# connector1.net
KiCad netlist of a schematic drawn in Altium Designer
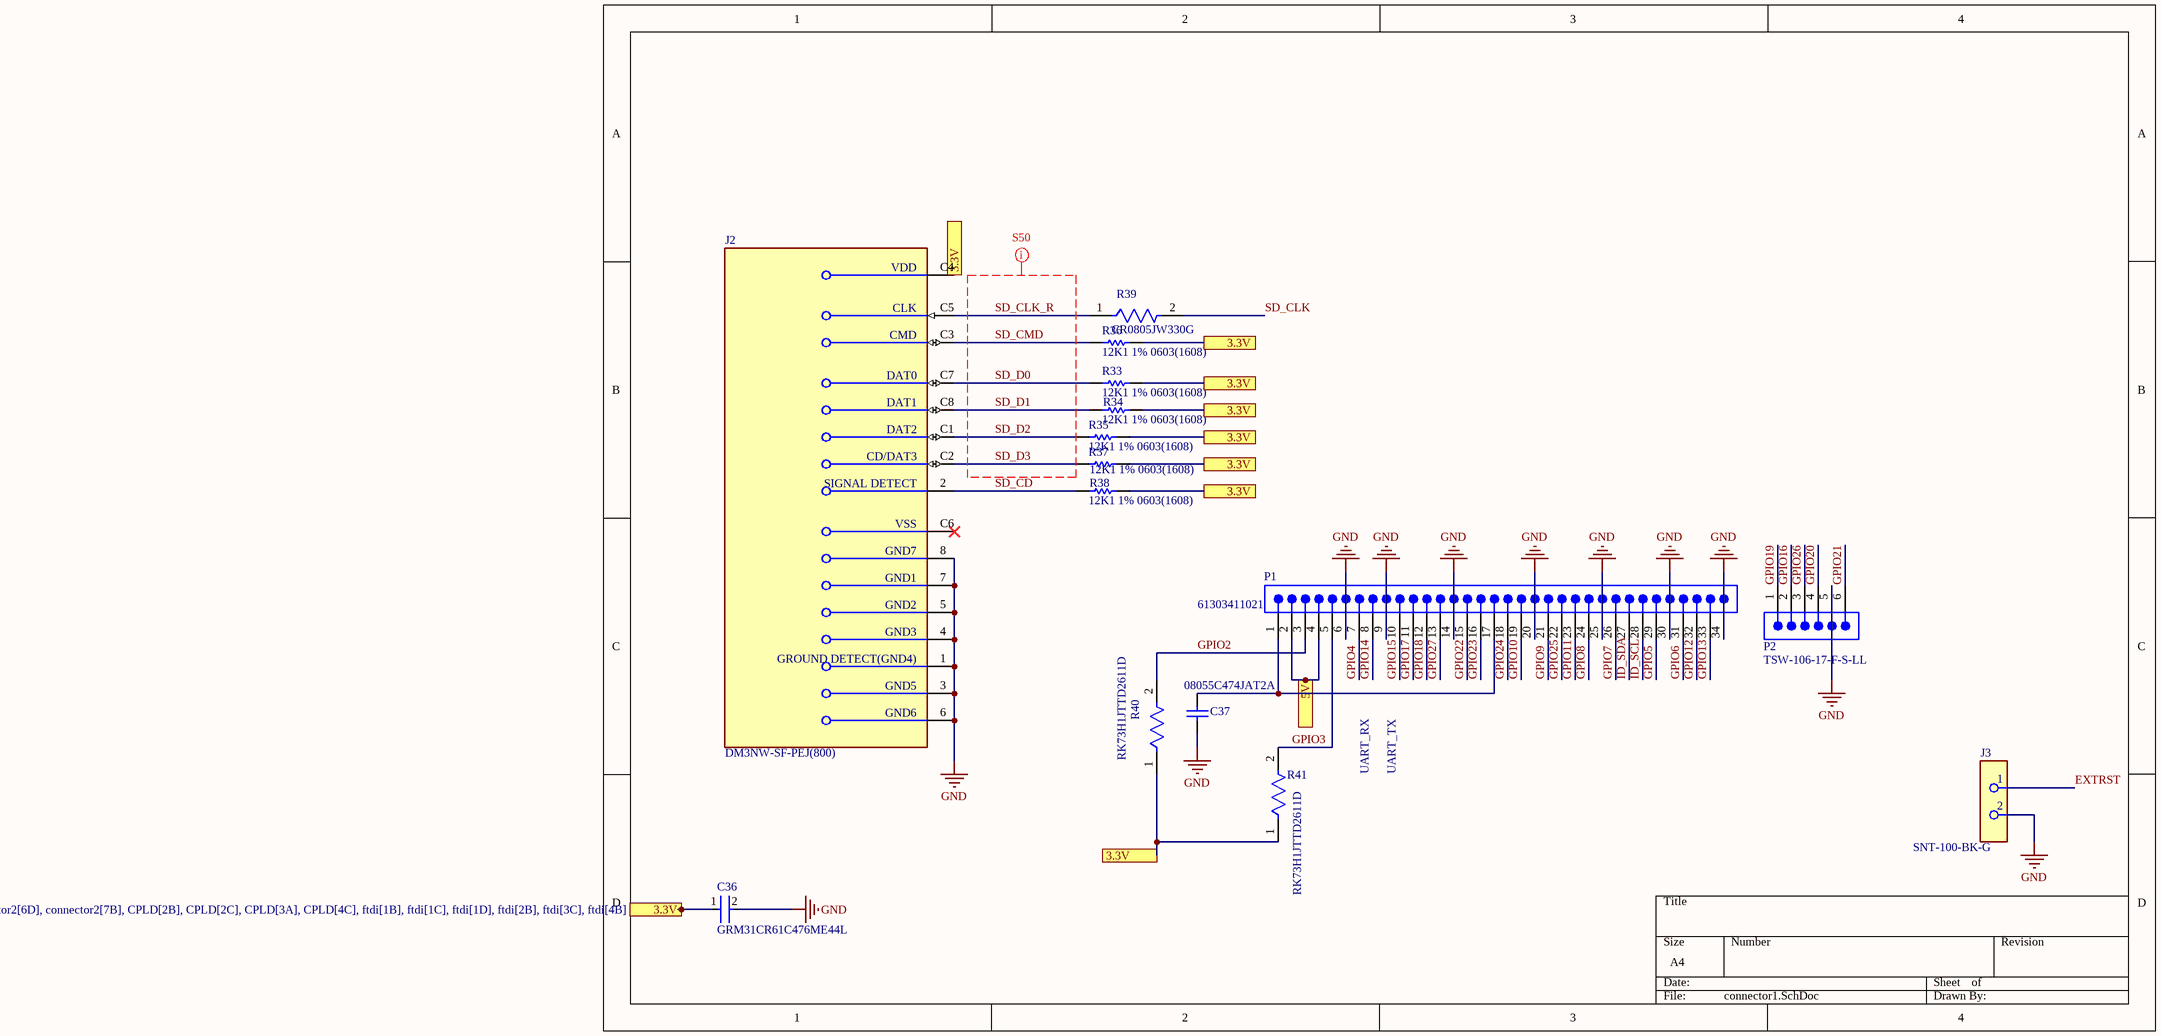
[diagram p0: connector1.SchDoc]

(export (version "E")
  (design (tool "Eeschema 10.0.6"))
  (components
    (comp (ref "C36")
      (value "GRM31CR61C476ME44L")
      (footprint "FP-GRM31C-0_3-e0_3_0_8-IPC_C")
      (description "Chip Multilayer Ceramic Capacitors for General Purpose, 1206, 47uF, X5R, 15%, 20%, 16V")
      (fields (field (name "TOLERANCE") "20%"))
      (libsource (lib "Altium Content Vault") (part "f23184f103b6ebe33a8c269c53dcba6"))
    )
    (comp (ref "C37")
      (value "08055C474JAT2A")
      (footprint "CAPC2013X140X50ML20T25")
      (fields (field (name "MANUFACTURER") "AVX Interconnect / Elco"))
      (libsource (lib "Altium Content Vault") (part "CAP"))
    )
    (comp (ref "J2")
      (value "DM3NW-SF-PEJ(800)")
      (footprint "FP-DM3NW-SF-PEJ_800-MFG")
      (description "CONN MICROSD CARD PUSH-PUSH SMD")
      (libsource (lib "Altium Content Vault") (part "c4d74c69e72bf12f873f0521b7ad6d9"))
    )
    (comp (ref "J3")
      (value "SNT-100-BK-G")
      (footprint "FP-SNT-100-BK-G-MFG")
      (description "CONN SHUNT 2POS")
      (libsource (lib "Altium Content Vault") (part "245d4dded57b275ea2dfe9722bb6e84"))
    )
    (comp (ref "P1")
      (value "61303411021")
      (footprint "61303411021")
      (libsource (lib "Altium Content Vault") (part "Header_Male_1R_34P"))
    )
    (comp (ref "P2")
      (value "TSW-106-17-F-S-LL")
      (footprint "SMTC-TSW-106-17-X-S-LL")
      (description "0.025\" SQ Post Header, Through-hole, Vertical, -55 to 125 degC, 2.54 mm Pitch, 6-Pin, Male, RoHS")
      (fields (field (name "MANUFACTURER") "Samtec"))
      (libsource (lib "Altium Content Vault") (part "SMTC-TSW-106-X-X-S-X"))
    )
    (comp (ref "R33")
      (value "12K1 1% 0603(1608)")
      (footprint "RESC0603(1608)_M")
      (description "12K1 0.1W 1% 0603 (1608 Metric)  SMD")
      (fields (field (name "POWER") "0.1 W") (field (name "TOLERANCE") "1 %"))
      (libsource (lib "Altium Content Vault") (part "RES"))
    )
    (comp (ref "R34")
      (value "12K1 1% 0603(1608)")
      (footprint "RESC0603(1608)_M")
      (description "12K1 0.1W 1% 0603 (1608 Metric)  SMD")
      (fields (field (name "POWER") "0.1 W") (field (name "TOLERANCE") "1 %"))
      (libsource (lib "Altium Content Vault") (part "RES"))
    )
    (comp (ref "R35")
      (value "12K1 1% 0603(1608)")
      (footprint "RESC0603(1608)_M")
      (description "12K1 0.1W 1% 0603 (1608 Metric)  SMD")
      (fields (field (name "POWER") "0.1 W") (field (name "TOLERANCE") "1 %"))
      (libsource (lib "Altium Content Vault") (part "RES"))
    )
    (comp (ref "R36")
      (value "12K1 1% 0603(1608)")
      (footprint "RESC0603(1608)_M")
      (description "12K1 0.1W 1% 0603 (1608 Metric)  SMD")
      (fields (field (name "POWER") "0.1 W") (field (name "TOLERANCE") "1 %"))
      (libsource (lib "Altium Content Vault") (part "RES"))
    )
    (comp (ref "R37")
      (value "12K1 1% 0603(1608)")
      (footprint "RESC0603(1608)_M")
      (description "12K1 0.1W 1% 0603 (1608 Metric)  SMD")
      (fields (field (name "POWER") "0.1 W") (field (name "TOLERANCE") "1 %"))
      (libsource (lib "Altium Content Vault") (part "RES"))
    )
    (comp (ref "R38")
      (value "12K1 1% 0603(1608)")
      (footprint "RESC0603(1608)_M")
      (description "12K1 0.1W 1% 0603 (1608 Metric)  SMD")
      (fields (field (name "POWER") "0.1 W") (field (name "TOLERANCE") "1 %"))
      (libsource (lib "Altium Content Vault") (part "RES"))
    )
    (comp (ref "R39")
      (value "CR0805JW330G")
      (footprint "FP-CR0805-IPC_C")
      (description "Thick Film Chip Resistors 0805 33Ω 0.125W 5% 200ppm/°C")
      (fields (field (name "TOLERANCE") "5%"))
      (libsource (lib "Altium Content Vault") (part "1029c3af85768c4190bb7ad29bc67b5"))
    )
    (comp (ref "R40")
      (value "RK73H1JTTD2611D")
      (footprint "FP-RK73H1J-IPC_B")
      (description "2.61kΩ ±0.5% 0.1W Chip Resistor 0603 Thick Film AEC-Q200 Qualified")
      (libsource (lib "Altium Content Vault") (part "1029c3af85768c4190bb7ad29bc67b5"))
    )
    (comp (ref "R41")
      (value "RK73H1JTTD2611D")
      (footprint "FP-RK73H1J-IPC_B")
      (description "2.61kΩ ±0.5% 0.1W Chip Resistor 0603 Thick Film AEC-Q200 Qualified")
      (libsource (lib "Altium Content Vault") (part "1029c3af85768c4190bb7ad29bc67b5"))
    )
  )
  (nets
    (net (code "1") (name "/3.3V") (class "Default")
      (node (ref "C36") (pin "1") (pinfunction "1_1") (pintype "passive"))
      (node (ref "J2") (pin "C4") (pinfunction "VDD_C4") (pintype "power_in"))
      (node (ref "R33") (pin "2") (pinfunction "2_2") (pintype "passive"))
      (node (ref "R34") (pin "2") (pinfunction "2_2") (pintype "passive"))
      (node (ref "R35") (pin "2") (pinfunction "2_2") (pintype "passive"))
      (node (ref "R36") (pin "2") (pinfunction "2_2") (pintype "passive"))
      (node (ref "R37") (pin "2") (pinfunction "2_2") (pintype "passive"))
      (node (ref "R38") (pin "2") (pinfunction "2_2") (pintype "passive"))
      (node (ref "R40") (pin "1") (pinfunction "1_1") (pintype "passive"))
      (node (ref "R41") (pin "1") (pinfunction "1_1") (pintype "passive"))
    )
    (net (code "2") (name "/5V") (class "Default")
      (node (ref "P1") (pin "2") (pinfunction "2_2") (pintype "passive"))
      (node (ref "P1") (pin "4") (pinfunction "4_4") (pintype "passive"))
    )
    (net (code "4") (name "/GPIO2") (class "Default")
      (node (ref "P1") (pin "3") (pinfunction "3_3") (pintype "passive"))
      (node (ref "R40") (pin "2") (pinfunction "2_2") (pintype "passive"))
    )
    (net (code "5") (name "/GPIO3") (class "Default")
      (node (ref "P1") (pin "5") (pinfunction "5_5") (pintype "passive"))
      (node (ref "R41") (pin "2") (pinfunction "2_2") (pintype "passive"))
    )
    (net (code "6") (name "/GPIO4") (class "Default")
      (node (ref "P1") (pin "7") (pinfunction "7_7") (pintype "passive"))
    )
    (net (code "7") (name "/GPIO5") (class "Default")
      (node (ref "P1") (pin "29") (pinfunction "29_29") (pintype "passive"))
    )
    (net (code "8") (name "/GPIO6") (class "Default")
      (node (ref "P1") (pin "31") (pinfunction "31_31") (pintype "passive"))
    )
    (net (code "9") (name "/GPIO7") (class "Default")
      (node (ref "P1") (pin "26") (pinfunction "26_26") (pintype "passive"))
    )
    (net (code "10") (name "/GPIO8") (class "Default")
      (node (ref "P1") (pin "24") (pinfunction "24_24") (pintype "passive"))
    )
    (net (code "11") (name "/GPIO9") (class "Default")
      (node (ref "P1") (pin "21") (pinfunction "21_21") (pintype "passive"))
    )
    (net (code "12") (name "/GPIO10") (class "Default")
      (node (ref "P1") (pin "19") (pinfunction "19_19") (pintype "passive"))
    )
    (net (code "13") (name "/GPIO11") (class "Default")
      (node (ref "P1") (pin "23") (pinfunction "23_23") (pintype "passive"))
    )
    (net (code "14") (name "/GPIO12") (class "Default")
      (node (ref "P1") (pin "32") (pinfunction "32_32") (pintype "passive"))
    )
    (net (code "15") (name "/GPIO13") (class "Default")
      (node (ref "P1") (pin "33") (pinfunction "33_33") (pintype "passive"))
    )
    (net (code "16") (name "/GPIO14") (class "Default")
      (node (ref "P1") (pin "8") (pinfunction "8_8") (pintype "passive"))
    )
    (net (code "17") (name "/GPIO15") (class "Default")
      (node (ref "P1") (pin "10") (pinfunction "10_10") (pintype "passive"))
    )
    (net (code "18") (name "/GPIO16") (class "Default")
      (node (ref "P2") (pin "2") (pinfunction "2_2") (pintype "passive"))
    )
    (net (code "19") (name "/GPIO17") (class "Default")
      (node (ref "P1") (pin "11") (pinfunction "11_11") (pintype "passive"))
    )
    (net (code "20") (name "/GPIO18") (class "Default")
      (node (ref "P1") (pin "12") (pinfunction "12_12") (pintype "passive"))
    )
    (net (code "21") (name "/GPIO19") (class "Default")
      (node (ref "P2") (pin "1") (pinfunction "1_1") (pintype "passive"))
    )
    (net (code "22") (name "/GPIO20") (class "Default")
      (node (ref "P2") (pin "4") (pinfunction "4_4") (pintype "passive"))
    )
    (net (code "23") (name "/GPIO21") (class "Default")
      (node (ref "P2") (pin "6") (pinfunction "6_6") (pintype "passive"))
    )
    (net (code "24") (name "/GPIO22") (class "Default")
      (node (ref "P1") (pin "15") (pinfunction "15_15") (pintype "passive"))
    )
    (net (code "25") (name "/GPIO23") (class "Default")
      (node (ref "P1") (pin "16") (pinfunction "16_16") (pintype "passive"))
    )
    (net (code "26") (name "/GPIO24") (class "Default")
      (node (ref "P1") (pin "18") (pinfunction "18_18") (pintype "passive"))
    )
    (net (code "27") (name "/GPIO25") (class "Default")
      (node (ref "P1") (pin "22") (pinfunction "22_22") (pintype "passive"))
    )
    (net (code "28") (name "/GPIO26") (class "Default")
      (node (ref "P2") (pin "3") (pinfunction "3_3") (pintype "passive"))
    )
    (net (code "29") (name "/GPIO27") (class "Default")
      (node (ref "P1") (pin "13") (pinfunction "13_13") (pintype "passive"))
    )
    (net (code "30") (name "/ID_SCL") (class "Default")
      (node (ref "P1") (pin "28") (pinfunction "28_28") (pintype "passive"))
    )
    (net (code "31") (name "/ID_SDA") (class "Default")
      (node (ref "P1") (pin "27") (pinfunction "27_27") (pintype "passive"))
    )
    (net (code "32") (name "/SD_CD") (class "Default")
      (node (ref "J2") (pin "2") (pinfunction "SIGNAL_DETECT_2") (pintype "power_in"))
      (node (ref "R38") (pin "1") (pinfunction "1_1") (pintype "passive"))
    )
    (net (code "33") (name "/SD_CLK") (class "Default")
      (node (ref "R39") (pin "2") (pinfunction "2_2") (pintype "passive"))
    )
    (net (code "34") (name "/SD_CLK_R") (class "Default")
      (node (ref "J2") (pin "C5") (pinfunction "CLK_C5") (pintype "input"))
      (node (ref "R39") (pin "1") (pinfunction "1_1") (pintype "passive"))
    )
    (net (code "35") (name "/SD_CMD") (class "Default")
      (node (ref "J2") (pin "C3") (pinfunction "CMD_C3") (pintype "bidirectional"))
      (node (ref "R36") (pin "1") (pinfunction "1_1") (pintype "passive"))
    )
    (net (code "36") (name "/SD_D0") (class "Default")
      (node (ref "J2") (pin "C7") (pinfunction "DAT0_C7") (pintype "bidirectional"))
      (node (ref "R33") (pin "1") (pinfunction "1_1") (pintype "passive"))
    )
    (net (code "37") (name "/SD_D1") (class "Default")
      (node (ref "J2") (pin "C8") (pinfunction "DAT1_C8") (pintype "bidirectional"))
      (node (ref "R34") (pin "1") (pinfunction "1_1") (pintype "passive"))
    )
    (net (code "38") (name "/SD_D2") (class "Default")
      (node (ref "J2") (pin "C1") (pinfunction "DAT2_C1") (pintype "bidirectional"))
      (node (ref "R35") (pin "1") (pinfunction "1_1") (pintype "passive"))
    )
    (net (code "39") (name "/SD_D3") (class "Default")
      (node (ref "J2") (pin "C2") (pinfunction "CD/DAT3_C2") (pintype "bidirectional"))
      (node (ref "R37") (pin "1") (pinfunction "1_1") (pintype "passive"))
    )
    (net (code "40") (name "GND") (class "Default")
      (node (ref "C36") (pin "2") (pinfunction "2_2") (pintype "passive"))
      (node (ref "C37") (pin "1") (pinfunction "1_1") (pintype "passive"))
      (node (ref "J2") (pin "1") (pinfunction "GROUND_DETECT(GND4)_1") (pintype "power_in"))
      (node (ref "J2") (pin "3") (pinfunction "GND5_3") (pintype "power_in"))
      (node (ref "J2") (pin "4") (pinfunction "GND3_4") (pintype "power_in"))
      (node (ref "J2") (pin "5") (pinfunction "GND2_5") (pintype "power_in"))
      (node (ref "J2") (pin "6") (pinfunction "GND6_6") (pintype "power_in"))
      (node (ref "J2") (pin "7") (pinfunction "GND1_7") (pintype "power_in"))
      (node (ref "J2") (pin "8") (pinfunction "GND7_8") (pintype "power_in"))
      (node (ref "P1") (pin "14") (pinfunction "14_14") (pintype "passive"))
      (node (ref "P1") (pin "20") (pinfunction "20_20") (pintype "passive"))
      (node (ref "P1") (pin "25") (pinfunction "25_25") (pintype "passive"))
      (node (ref "P1") (pin "30") (pinfunction "30_30") (pintype "passive"))
      (node (ref "P1") (pin "34") (pinfunction "34_34") (pintype "passive"))
      (node (ref "P1") (pin "6") (pinfunction "6_6") (pintype "passive"))
      (node (ref "P1") (pin "9") (pinfunction "9_9") (pintype "passive"))
      (node (ref "P2") (pin "5") (pinfunction "5_5") (pintype "passive"))
    )
    (net (code "41") (name "Net-(C37-Pad2)") (class "Default")
      (node (ref "C37") (pin "2") (pinfunction "2_2") (pintype "passive"))
      (node (ref "P1") (pin "1") (pinfunction "1_1") (pintype "passive"))
      (node (ref "P1") (pin "17") (pinfunction "17_17") (pintype "passive"))
    )
    (net (code "42") (name "unconnected-(J2-VSS-PadC6)") (class "Default")
      (node (ref "J2") (pin "C6") (pinfunction "VSS_C6") (pintype "power_in+no_connect"))
    )
  )
)
